# 2_matrix.net
KiCad netlist of a schematic drawn in Altium Designer
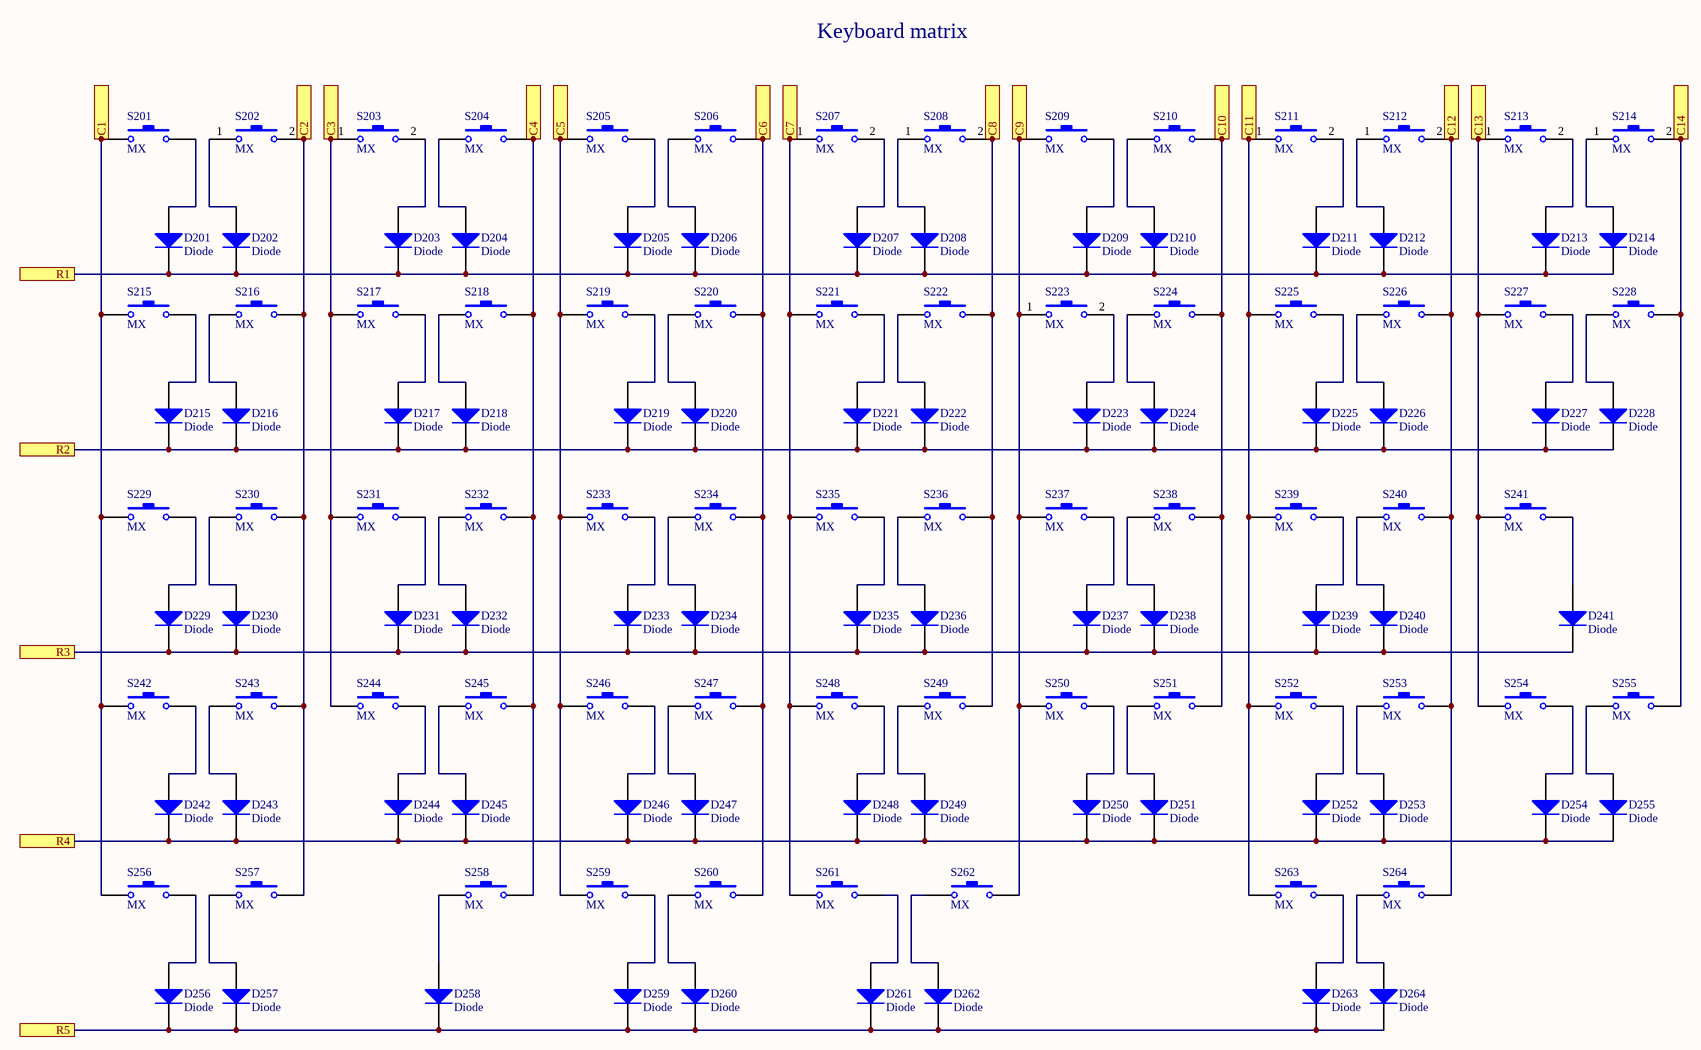
[diagram p0: 2_matrix.SchDoc]

(export (version "E")
  (design (tool "Eeschema 10.0.6"))
  (components
    (comp (ref "D201")
      (value "Diode")
      (footprint "SOD-123")
      (description "Default Diode")
      (fields (field (name "LCSC PART #") "C81598") (field (name "MRF.PART") "1N4148W"))
      (libsource (lib "Miscellaneous Devices") (part "Diode"))
    )
    (comp (ref "D202")
      (value "Diode")
      (footprint "SOD-123")
      (description "Default Diode")
      (fields (field (name "LCSC PART #") "C81598") (field (name "MRF.PART") "1N4148W"))
      (libsource (lib "Miscellaneous Devices") (part "Diode"))
    )
    (comp (ref "D203")
      (value "Diode")
      (footprint "SOD-123")
      (description "Default Diode")
      (fields (field (name "LCSC PART #") "C81598") (field (name "MRF.PART") "1N4148W"))
      (libsource (lib "Miscellaneous Devices") (part "Diode"))
    )
    (comp (ref "D204")
      (value "Diode")
      (footprint "SOD-123")
      (description "Default Diode")
      (fields (field (name "LCSC PART #") "C81598") (field (name "MRF.PART") "1N4148W"))
      (libsource (lib "Miscellaneous Devices") (part "Diode"))
    )
    (comp (ref "D205")
      (value "Diode")
      (footprint "SOD-123")
      (description "Default Diode")
      (fields (field (name "LCSC PART #") "C81598") (field (name "MRF.PART") "1N4148W"))
      (libsource (lib "Miscellaneous Devices") (part "Diode"))
    )
    (comp (ref "D206")
      (value "Diode")
      (footprint "SOD-123")
      (description "Default Diode")
      (fields (field (name "LCSC PART #") "C81598") (field (name "MRF.PART") "1N4148W"))
      (libsource (lib "Miscellaneous Devices") (part "Diode"))
    )
    (comp (ref "D207")
      (value "Diode")
      (footprint "SOD-123")
      (description "Default Diode")
      (fields (field (name "LCSC PART #") "C81598") (field (name "MRF.PART") "1N4148W"))
      (libsource (lib "Miscellaneous Devices") (part "Diode"))
    )
    (comp (ref "D208")
      (value "Diode")
      (footprint "SOD-123")
      (description "Default Diode")
      (fields (field (name "LCSC PART #") "C81598") (field (name "MRF.PART") "1N4148W"))
      (libsource (lib "Miscellaneous Devices") (part "Diode"))
    )
    (comp (ref "D209")
      (value "Diode")
      (footprint "SOD-123")
      (description "Default Diode")
      (fields (field (name "LCSC PART #") "C81598") (field (name "MRF.PART") "1N4148W"))
      (libsource (lib "Miscellaneous Devices") (part "Diode"))
    )
    (comp (ref "D210")
      (value "Diode")
      (footprint "SOD-123")
      (description "Default Diode")
      (fields (field (name "LCSC PART #") "C81598") (field (name "MRF.PART") "1N4148W"))
      (libsource (lib "Miscellaneous Devices") (part "Diode"))
    )
    (comp (ref "D211")
      (value "Diode")
      (footprint "SOD-123")
      (description "Default Diode")
      (fields (field (name "LCSC PART #") "C81598") (field (name "MRF.PART") "1N4148W"))
      (libsource (lib "Miscellaneous Devices") (part "Diode"))
    )
    (comp (ref "D212")
      (value "Diode")
      (footprint "SOD-123")
      (description "Default Diode")
      (fields (field (name "LCSC PART #") "C81598") (field (name "MRF.PART") "1N4148W"))
      (libsource (lib "Miscellaneous Devices") (part "Diode"))
    )
    (comp (ref "D213")
      (value "Diode")
      (footprint "SOD-123")
      (description "Default Diode")
      (fields (field (name "LCSC PART #") "C81598") (field (name "MRF.PART") "1N4148W"))
      (libsource (lib "Miscellaneous Devices") (part "Diode"))
    )
    (comp (ref "D214")
      (value "Diode")
      (footprint "SOD-123")
      (description "Default Diode")
      (fields (field (name "LCSC PART #") "C81598") (field (name "MRF.PART") "1N4148W"))
      (libsource (lib "Miscellaneous Devices") (part "Diode"))
    )
    (comp (ref "D215")
      (value "Diode")
      (footprint "SOD-123")
      (description "Default Diode")
      (fields (field (name "LCSC PART #") "C81598") (field (name "MRF.PART") "1N4148W"))
      (libsource (lib "Miscellaneous Devices") (part "Diode"))
    )
    (comp (ref "D216")
      (value "Diode")
      (footprint "SOD-123")
      (description "Default Diode")
      (fields (field (name "LCSC PART #") "C81598") (field (name "MRF.PART") "1N4148W"))
      (libsource (lib "Miscellaneous Devices") (part "Diode"))
    )
    (comp (ref "D217")
      (value "Diode")
      (footprint "SOD-123")
      (description "Default Diode")
      (fields (field (name "LCSC PART #") "C81598") (field (name "MRF.PART") "1N4148W"))
      (libsource (lib "Miscellaneous Devices") (part "Diode"))
    )
    (comp (ref "D218")
      (value "Diode")
      (footprint "SOD-123")
      (description "Default Diode")
      (fields (field (name "LCSC PART #") "C81598") (field (name "MRF.PART") "1N4148W"))
      (libsource (lib "Miscellaneous Devices") (part "Diode"))
    )
    (comp (ref "D219")
      (value "Diode")
      (footprint "SOD-123")
      (description "Default Diode")
      (fields (field (name "LCSC PART #") "C81598") (field (name "MRF.PART") "1N4148W"))
      (libsource (lib "Miscellaneous Devices") (part "Diode"))
    )
    (comp (ref "D220")
      (value "Diode")
      (footprint "SOD-123")
      (description "Default Diode")
      (fields (field (name "LCSC PART #") "C81598") (field (name "MRF.PART") "1N4148W"))
      (libsource (lib "Miscellaneous Devices") (part "Diode"))
    )
    (comp (ref "D221")
      (value "Diode")
      (footprint "SOD-123")
      (description "Default Diode")
      (fields (field (name "LCSC PART #") "C81598") (field (name "MRF.PART") "1N4148W"))
      (libsource (lib "Miscellaneous Devices") (part "Diode"))
    )
    (comp (ref "D222")
      (value "Diode")
      (footprint "SOD-123")
      (description "Default Diode")
      (fields (field (name "LCSC PART #") "C81598") (field (name "MRF.PART") "1N4148W"))
      (libsource (lib "Miscellaneous Devices") (part "Diode"))
    )
    (comp (ref "D223")
      (value "Diode")
      (footprint "SOD-123")
      (description "Default Diode")
      (fields (field (name "LCSC PART #") "C81598") (field (name "MRF.PART") "1N4148W"))
      (libsource (lib "Miscellaneous Devices") (part "Diode"))
    )
    (comp (ref "D224")
      (value "Diode")
      (footprint "SOD-123")
      (description "Default Diode")
      (fields (field (name "LCSC PART #") "C81598") (field (name "MRF.PART") "1N4148W"))
      (libsource (lib "Miscellaneous Devices") (part "Diode"))
    )
    (comp (ref "D225")
      (value "Diode")
      (footprint "SOD-123")
      (description "Default Diode")
      (fields (field (name "LCSC PART #") "C81598") (field (name "MRF.PART") "1N4148W"))
      (libsource (lib "Miscellaneous Devices") (part "Diode"))
    )
    (comp (ref "D226")
      (value "Diode")
      (footprint "SOD-123")
      (description "Default Diode")
      (fields (field (name "LCSC PART #") "C81598") (field (name "MRF.PART") "1N4148W"))
      (libsource (lib "Miscellaneous Devices") (part "Diode"))
    )
    (comp (ref "D227")
      (value "Diode")
      (footprint "SOD-123")
      (description "Default Diode")
      (fields (field (name "LCSC PART #") "C81598") (field (name "MRF.PART") "1N4148W"))
      (libsource (lib "Miscellaneous Devices") (part "Diode"))
    )
    (comp (ref "D228")
      (value "Diode")
      (footprint "SOD-123")
      (description "Default Diode")
      (fields (field (name "LCSC PART #") "C81598") (field (name "MRF.PART") "1N4148W"))
      (libsource (lib "Miscellaneous Devices") (part "Diode"))
    )
    (comp (ref "D229")
      (value "Diode")
      (footprint "SOD-123")
      (description "Default Diode")
      (fields (field (name "LCSC PART #") "C81598") (field (name "MRF.PART") "1N4148W"))
      (libsource (lib "Miscellaneous Devices") (part "Diode"))
    )
    (comp (ref "D230")
      (value "Diode")
      (footprint "SOD-123")
      (description "Default Diode")
      (fields (field (name "LCSC PART #") "C81598") (field (name "MRF.PART") "1N4148W"))
      (libsource (lib "Miscellaneous Devices") (part "Diode"))
    )
    (comp (ref "D231")
      (value "Diode")
      (footprint "SOD-123")
      (description "Default Diode")
      (fields (field (name "LCSC PART #") "C81598") (field (name "MRF.PART") "1N4148W"))
      (libsource (lib "Miscellaneous Devices") (part "Diode"))
    )
    (comp (ref "D232")
      (value "Diode")
      (footprint "SOD-123")
      (description "Default Diode")
      (fields (field (name "LCSC PART #") "C81598") (field (name "MRF.PART") "1N4148W"))
      (libsource (lib "Miscellaneous Devices") (part "Diode"))
    )
    (comp (ref "D233")
      (value "Diode")
      (footprint "SOD-123")
      (description "Default Diode")
      (fields (field (name "LCSC PART #") "C81598") (field (name "MRF.PART") "1N4148W"))
      (libsource (lib "Miscellaneous Devices") (part "Diode"))
    )
    (comp (ref "D234")
      (value "Diode")
      (footprint "SOD-123")
      (description "Default Diode")
      (fields (field (name "LCSC PART #") "C81598") (field (name "MRF.PART") "1N4148W"))
      (libsource (lib "Miscellaneous Devices") (part "Diode"))
    )
    (comp (ref "D235")
      (value "Diode")
      (footprint "SOD-123")
      (description "Default Diode")
      (fields (field (name "LCSC PART #") "C81598") (field (name "MRF.PART") "1N4148W"))
      (libsource (lib "Miscellaneous Devices") (part "Diode"))
    )
    (comp (ref "D236")
      (value "Diode")
      (footprint "SOD-123")
      (description "Default Diode")
      (fields (field (name "LCSC PART #") "C81598") (field (name "MRF.PART") "1N4148W"))
      (libsource (lib "Miscellaneous Devices") (part "Diode"))
    )
    (comp (ref "D237")
      (value "Diode")
      (footprint "SOD-123")
      (description "Default Diode")
      (fields (field (name "LCSC PART #") "C81598") (field (name "MRF.PART") "1N4148W"))
      (libsource (lib "Miscellaneous Devices") (part "Diode"))
    )
    (comp (ref "D238")
      (value "Diode")
      (footprint "SOD-123")
      (description "Default Diode")
      (fields (field (name "LCSC PART #") "C81598") (field (name "MRF.PART") "1N4148W"))
      (libsource (lib "Miscellaneous Devices") (part "Diode"))
    )
    (comp (ref "D239")
      (value "Diode")
      (footprint "SOD-123")
      (description "Default Diode")
      (fields (field (name "LCSC PART #") "C81598") (field (name "MRF.PART") "1N4148W"))
      (libsource (lib "Miscellaneous Devices") (part "Diode"))
    )
    (comp (ref "D240")
      (value "Diode")
      (footprint "SOD-123")
      (description "Default Diode")
      (fields (field (name "LCSC PART #") "C81598") (field (name "MRF.PART") "1N4148W"))
      (libsource (lib "Miscellaneous Devices") (part "Diode"))
    )
    (comp (ref "D241")
      (value "Diode")
      (footprint "SOD-123")
      (description "Default Diode")
      (fields (field (name "LCSC PART #") "C81598") (field (name "MRF.PART") "1N4148W"))
      (libsource (lib "Miscellaneous Devices") (part "Diode"))
    )
    (comp (ref "D242")
      (value "Diode")
      (footprint "SOD-123")
      (description "Default Diode")
      (fields (field (name "LCSC PART #") "C81598") (field (name "MRF.PART") "1N4148W"))
      (libsource (lib "Miscellaneous Devices") (part "Diode"))
    )
    (comp (ref "D243")
      (value "Diode")
      (footprint "SOD-123")
      (description "Default Diode")
      (fields (field (name "LCSC PART #") "C81598") (field (name "MRF.PART") "1N4148W"))
      (libsource (lib "Miscellaneous Devices") (part "Diode"))
    )
    (comp (ref "D244")
      (value "Diode")
      (footprint "SOD-123")
      (description "Default Diode")
      (fields (field (name "LCSC PART #") "C81598") (field (name "MRF.PART") "1N4148W"))
      (libsource (lib "Miscellaneous Devices") (part "Diode"))
    )
    (comp (ref "D245")
      (value "Diode")
      (footprint "SOD-123")
      (description "Default Diode")
      (fields (field (name "LCSC PART #") "C81598") (field (name "MRF.PART") "1N4148W"))
      (libsource (lib "Miscellaneous Devices") (part "Diode"))
    )
    (comp (ref "D246")
      (value "Diode")
      (footprint "SOD-123")
      (description "Default Diode")
      (fields (field (name "LCSC PART #") "C81598") (field (name "MRF.PART") "1N4148W"))
      (libsource (lib "Miscellaneous Devices") (part "Diode"))
    )
    (comp (ref "D247")
      (value "Diode")
      (footprint "SOD-123")
      (description "Default Diode")
      (fields (field (name "LCSC PART #") "C81598") (field (name "MRF.PART") "1N4148W"))
      (libsource (lib "Miscellaneous Devices") (part "Diode"))
    )
    (comp (ref "D248")
      (value "Diode")
      (footprint "SOD-123")
      (description "Default Diode")
      (fields (field (name "LCSC PART #") "C81598") (field (name "MRF.PART") "1N4148W"))
      (libsource (lib "Miscellaneous Devices") (part "Diode"))
    )
    (comp (ref "D249")
      (value "Diode")
      (footprint "SOD-123")
      (description "Default Diode")
      (fields (field (name "LCSC PART #") "C81598") (field (name "MRF.PART") "1N4148W"))
      (libsource (lib "Miscellaneous Devices") (part "Diode"))
    )
    (comp (ref "D250")
      (value "Diode")
      (footprint "SOD-123")
      (description "Default Diode")
      (fields (field (name "LCSC PART #") "C81598") (field (name "MRF.PART") "1N4148W"))
      (libsource (lib "Miscellaneous Devices") (part "Diode"))
    )
    (comp (ref "D251")
      (value "Diode")
      (footprint "SOD-123")
      (description "Default Diode")
      (fields (field (name "LCSC PART #") "C81598") (field (name "MRF.PART") "1N4148W"))
      (libsource (lib "Miscellaneous Devices") (part "Diode"))
    )
    (comp (ref "D252")
      (value "Diode")
      (footprint "SOD-123")
      (description "Default Diode")
      (fields (field (name "LCSC PART #") "C81598") (field (name "MRF.PART") "1N4148W"))
      (libsource (lib "Miscellaneous Devices") (part "Diode"))
    )
    (comp (ref "D253")
      (value "Diode")
      (footprint "SOD-123")
      (description "Default Diode")
      (fields (field (name "LCSC PART #") "C81598") (field (name "MRF.PART") "1N4148W"))
      (libsource (lib "Miscellaneous Devices") (part "Diode"))
    )
    (comp (ref "D254")
      (value "Diode")
      (footprint "SOD-123")
      (description "Default Diode")
      (fields (field (name "LCSC PART #") "C81598") (field (name "MRF.PART") "1N4148W"))
      (libsource (lib "Miscellaneous Devices") (part "Diode"))
    )
    (comp (ref "D255")
      (value "Diode")
      (footprint "SOD-123")
      (description "Default Diode")
      (fields (field (name "LCSC PART #") "C81598") (field (name "MRF.PART") "1N4148W"))
      (libsource (lib "Miscellaneous Devices") (part "Diode"))
    )
    (comp (ref "D256")
      (value "Diode")
      (footprint "SOD-123")
      (description "Default Diode")
      (fields (field (name "LCSC PART #") "C81598") (field (name "MRF.PART") "1N4148W"))
      (libsource (lib "Miscellaneous Devices") (part "Diode"))
    )
    (comp (ref "D257")
      (value "Diode")
      (footprint "SOD-123")
      (description "Default Diode")
      (fields (field (name "LCSC PART #") "C81598") (field (name "MRF.PART") "1N4148W"))
      (libsource (lib "Miscellaneous Devices") (part "Diode"))
    )
    (comp (ref "D258")
      (value "Diode")
      (footprint "SOD-123")
      (description "Default Diode")
      (fields (field (name "LCSC PART #") "C81598") (field (name "MRF.PART") "1N4148W"))
      (libsource (lib "Miscellaneous Devices") (part "Diode"))
    )
    (comp (ref "D259")
      (value "Diode")
      (footprint "SOD-123")
      (description "Default Diode")
      (fields (field (name "LCSC PART #") "C81598") (field (name "MRF.PART") "1N4148W"))
      (libsource (lib "Miscellaneous Devices") (part "Diode"))
    )
    (comp (ref "D260")
      (value "Diode")
      (footprint "SOD-123")
      (description "Default Diode")
      (fields (field (name "LCSC PART #") "C81598") (field (name "MRF.PART") "1N4148W"))
      (libsource (lib "Miscellaneous Devices") (part "Diode"))
    )
    (comp (ref "D261")
      (value "Diode")
      (footprint "SOD-123")
      (description "Default Diode")
      (fields (field (name "LCSC PART #") "C81598") (field (name "MRF.PART") "1N4148W"))
      (libsource (lib "Miscellaneous Devices") (part "Diode"))
    )
    (comp (ref "D262")
      (value "Diode")
      (footprint "SOD-123")
      (description "Default Diode")
      (fields (field (name "LCSC PART #") "C81598") (field (name "MRF.PART") "1N4148W"))
      (libsource (lib "Miscellaneous Devices") (part "Diode"))
    )
    (comp (ref "D263")
      (value "Diode")
      (footprint "SOD-123")
      (description "Default Diode")
      (fields (field (name "LCSC PART #") "C81598") (field (name "MRF.PART") "1N4148W"))
      (libsource (lib "Miscellaneous Devices") (part "Diode"))
    )
    (comp (ref "D264")
      (value "Diode")
      (footprint "SOD-123")
      (description "Default Diode")
      (fields (field (name "LCSC PART #") "C81598") (field (name "MRF.PART") "1N4148W"))
      (libsource (lib "Miscellaneous Devices") (part "Diode"))
    )
    (comp (ref "S201")
      (value "MX")
      (footprint "ALPS-switch - 1.25U - switched pol")
      (description "Switch")
      (libsource (lib "Miscellaneous Devices") (part "SW-PB"))
    )
    (comp (ref "S202")
      (value "MX")
      (footprint "Alps-switch - switched pol")
      (description "Switch")
      (libsource (lib "") (part "SW-PB_2"))
    )
    (comp (ref "S203")
      (value "MX")
      (footprint "Alps-switch")
      (description "Switch")
      (libsource (lib "") (part "SW-PB_2"))
    )
    (comp (ref "S204")
      (value "MX")
      (footprint "Alps-switch")
      (description "Switch")
      (libsource (lib "Miscellaneous Devices") (part "SW-PB"))
    )
    (comp (ref "S205")
      (value "MX")
      (footprint "Alps-switch")
      (description "Switch")
      (libsource (lib "Miscellaneous Devices") (part "SW-PB"))
    )
    (comp (ref "S206")
      (value "MX")
      (footprint "Alps-switch - switched pol")
      (description "Switch")
      (libsource (lib "Miscellaneous Devices") (part "SW-PB"))
    )
    (comp (ref "S207")
      (value "MX")
      (footprint "Alps-switch")
      (description "Switch")
      (libsource (lib "") (part "SW-PB_2"))
    )
    (comp (ref "S208")
      (value "MX")
      (footprint "Alps-switch - switched pol")
      (description "Switch")
      (libsource (lib "") (part "SW-PB_2"))
    )
    (comp (ref "S209")
      (value "MX")
      (footprint "Alps-switch")
      (description "Switch")
      (libsource (lib "Miscellaneous Devices") (part "SW-PB"))
    )
    (comp (ref "S210")
      (value "MX")
      (footprint "Alps-switch - switched pol")
      (description "Switch")
      (libsource (lib "Miscellaneous Devices") (part "SW-PB"))
    )
    (comp (ref "S211")
      (value "MX")
      (footprint "Alps-switch")
      (description "Switch")
      (libsource (lib "") (part "SW-PB_2"))
    )
    (comp (ref "S212")
      (value "MX")
      (footprint "Alps-switch - switched pol")
      (description "Switch")
      (libsource (lib "") (part "SW-PB_2"))
    )
    (comp (ref "S213")
      (value "MX")
      (footprint "Alps-switch")
      (description "Switch")
      (libsource (lib "") (part "SW-PB_2"))
    )
    (comp (ref "S214")
      (value "MX")
      (footprint "ALPS-switch - 1.25U - switched pol")
      (description "Switch")
      (libsource (lib "") (part "SW-PB_2"))
    )
    (comp (ref "S215")
      (value "MX")
      (footprint "ALPS-switch - 1.25U")
      (description "TAB")
      (libsource (lib "Miscellaneous Devices") (part "SW-PB"))
    )
    (comp (ref "S216")
      (value "MX")
      (footprint "Alps-switch")
      (description "Switch")
      (libsource (lib "Miscellaneous Devices") (part "SW-PB"))
    )
    (comp (ref "S217")
      (value "MX")
      (footprint "Alps-switch")
      (description "Switch")
      (libsource (lib "Miscellaneous Devices") (part "SW-PB"))
    )
    (comp (ref "S218")
      (value "MX")
      (footprint "Alps-switch - switched pol")
      (description "Switch")
      (libsource (lib "Miscellaneous Devices") (part "SW-PB"))
    )
    (comp (ref "S219")
      (value "MX")
      (footprint "Alps-switch")
      (description "Switch")
      (libsource (lib "Miscellaneous Devices") (part "SW-PB"))
    )
    (comp (ref "S220")
      (value "MX")
      (footprint "Alps-switch")
      (description "Switch")
      (libsource (lib "Miscellaneous Devices") (part "SW-PB"))
    )
    (comp (ref "S221")
      (value "MX")
      (footprint "Alps-switch")
      (description "Switch")
      (libsource (lib "Miscellaneous Devices") (part "SW-PB"))
    )
    (comp (ref "S222")
      (value "MX")
      (footprint "Alps-switch")
      (description "Switch")
      (libsource (lib "Miscellaneous Devices") (part "SW-PB"))
    )
    (comp (ref "S223")
      (value "MX")
      (footprint "Alps-switch")
      (description "Switch")
      (libsource (lib "") (part "SW-PB_2"))
    )
    (comp (ref "S224")
      (value "MX")
      (footprint "Alps-switch - switched pol")
      (description "Switch")
      (libsource (lib "Miscellaneous Devices") (part "SW-PB"))
    )
    (comp (ref "S225")
      (value "MX")
      (footprint "Alps-switch")
      (description "Switch")
      (libsource (lib "Miscellaneous Devices") (part "SW-PB"))
    )
    (comp (ref "S226")
      (value "MX")
      (footprint "Alps-switch - switched pol")
      (description "Switch")
      (libsource (lib "Miscellaneous Devices") (part "SW-PB"))
    )
    (comp (ref "S227")
      (value "MX")
      (footprint "Alps-switch")
      (description "Switch")
      (libsource (lib "") (part "SW-PB_1"))
    )
    (comp (ref "S228")
      (value "MX")
      (footprint "ALPS-SWITCH - ENTER - AEKISO")
      (description "Switch")
      (libsource (lib "Miscellaneous Devices") (part "SW-PB"))
    )
    (comp (ref "S229")
      (value "MX")
      (footprint "ALPS-switch - 2U - no stab")
      (description "Switch")
      (libsource (lib "Miscellaneous Devices") (part "SW-PB"))
    )
    (comp (ref "S230")
      (value "MX")
      (footprint "Alps-switch")
      (description "Switch")
      (libsource (lib "Miscellaneous Devices") (part "SW-PB"))
    )
    (comp (ref "S231")
      (value "MX")
      (footprint "Alps-switch")
      (description "Switch")
      (libsource (lib "Miscellaneous Devices") (part "SW-PB"))
    )
    (comp (ref "S232")
      (value "MX")
      (footprint "Alps-switch - switched pol")
      (description "Switch")
      (libsource (lib "Miscellaneous Devices") (part "SW-PB"))
    )
    (comp (ref "S233")
      (value "MX")
      (footprint "Alps-switch")
      (description "Switch")
      (libsource (lib "Miscellaneous Devices") (part "SW-PB"))
    )
    (comp (ref "S234")
      (value "MX")
      (footprint "Alps-switch - switched pol")
      (description "Switch")
      (libsource (lib "") (part "SW-PB_1"))
    )
    (comp (ref "S235")
      (value "MX")
      (footprint "Alps-switch - switched pol")
      (description "Switch")
      (libsource (lib "") (part "SW-PB_1"))
    )
    (comp (ref "S236")
      (value "MX")
      (footprint "Alps-switch")
      (description "Switch")
      (libsource (lib "") (part "SW-PB_1"))
    )
    (comp (ref "S237")
      (value "MX")
      (footprint "Alps-switch - switched pol")
      (description "Switch")
      (libsource (lib "") (part "SW-PB_1"))
    )
    (comp (ref "S238")
      (value "MX")
      (footprint "Alps-switch - switched pol")
      (description "Switch")
      (libsource (lib "Miscellaneous Devices") (part "SW-PB"))
    )
    (comp (ref "S239")
      (value "MX")
      (footprint "Alps-switch")
      (description "Switch")
      (libsource (lib "Miscellaneous Devices") (part "SW-PB"))
    )
    (comp (ref "S240")
      (value "MX")
      (footprint "Alps-switch - switched pol")
      (description "Switch")
      (libsource (lib "Miscellaneous Devices") (part "SW-PB"))
    )
    (comp (ref "S241")
      (value "MX")
      (footprint "Alps-switch")
      (description "Switch")
      (libsource (lib "Miscellaneous Devices") (part "SW-PB"))
    )
    (comp (ref "S242")
      (value "MX")
      (footprint "ALPS-switch - 1.5U")
      (description "Switch")
      (libsource (lib "Miscellaneous Devices") (part "SW-PB"))
    )
    (comp (ref "S243")
      (value "MX")
      (footprint "Alps-switch - switched pol")
      (description "Switch")
      (libsource (lib "Miscellaneous Devices") (part "SW-PB"))
    )
    (comp (ref "S244")
      (value "MX")
      (footprint "Alps-switch - switched pol")
      (description "Switch")
      (libsource (lib "") (part "SW-PB_1"))
    )
    (comp (ref "S245")
      (value "MX")
      (footprint "Alps-switch")
      (description "Switch")
      (libsource (lib "") (part "SW-PB_1"))
    )
    (comp (ref "S246")
      (value "MX")
      (footprint "Alps-switch - switched pol")
      (description "Switch")
      (libsource (lib "") (part "SW-PB_1"))
    )
    (comp (ref "S247")
      (value "MX")
      (footprint "Alps-switch")
      (description "Switch")
      (libsource (lib "") (part "SW-PB_1"))
    )
    (comp (ref "S248")
      (value "MX")
      (footprint "Alps-switch - switched pol")
      (description "Switch")
      (libsource (lib "") (part "SW-PB_1"))
    )
    (comp (ref "S249")
      (value "MX")
      (footprint "Alps-switch - switched pol")
      (description "Switch")
      (libsource (lib "Miscellaneous Devices") (part "SW-PB"))
    )
    (comp (ref "S250")
      (value "MX")
      (footprint "Alps-switch - switched pol")
      (description "Switch")
      (libsource (lib "") (part "SW-PB_1"))
    )
    (comp (ref "S251")
      (value "MX")
      (footprint "Alps-switch - switched pol")
      (description "Switch")
      (libsource (lib "Miscellaneous Devices") (part "SW-PB"))
    )
    (comp (ref "S252")
      (value "MX")
      (footprint "Alps-switch - switched pol")
      (description "Switch")
      (libsource (lib "") (part "SW-PB_1"))
    )
    (comp (ref "S253")
      (value "MX")
      (footprint "Alps-switch")
      (description "Switch")
      (libsource (lib "") (part "SW-PB_1"))
    )
    (comp (ref "S254")
      (value "MX")
      (footprint "ALPS-switch - AEKISO r_shift")
      (description "Switch")
      (libsource (lib "Miscellaneous Devices") (part "SW-PB"))
    )
    (comp (ref "S255")
      (value "MX")
      (footprint "Alps-switch")
      (description "Switch")
      (libsource (lib "Miscellaneous Devices") (part "SW-PB"))
    )
    (comp (ref "S256")
      (value "MX")
      (footprint "Alps-switch - switched pol")
      (description "Switch")
      (libsource (lib "Miscellaneous Devices") (part "SW-PB"))
    )
    (comp (ref "S257")
      (value "MX")
      (footprint "ALPS-switch - L_WIN - AEKISO60")
      (description "Switch")
      (libsource (lib "Miscellaneous Devices") (part "SW-PB"))
    )
    (comp (ref "S258")
      (value "MX")
      (footprint "ALPS-switch - L_alt - AEKISO60")
      (description "Switch")
      (libsource (lib "Miscellaneous Devices") (part "SW-PB"))
    )
    (comp (ref "S259")
      (value "MX")
      (footprint "ALPS-SWITCH - L SPLIT SPACE - AEKISO60")
      (description "Switch")
      (libsource (lib "Miscellaneous Devices") (part "SW-PB"))
    )
    (comp (ref "S260")
      (value "MX")
      (footprint "ALPS-SWITCH - SPACE - AEKISO60")
      (description "Switch")
      (libsource (lib "Miscellaneous Devices") (part "SW-PB"))
    )
    (comp (ref "S261")
      (value "MX")
      (footprint "ALPS-switch - R split space - AEKISO60")
      (description "Switch")
      (libsource (lib "Miscellaneous Devices") (part "SW-PB"))
    )
    (comp (ref "S262")
      (value "MX")
      (footprint "ALPS-switch - R_alt - AEKISO60")
      (description "Switch")
      (libsource (lib "Miscellaneous Devices") (part "SW-PB"))
    )
    (comp (ref "S263")
      (value "MX")
      (footprint "ALPS-SWITCH - R_WIN - AEKISO60")
      (description "Switch")
      (libsource (lib "Miscellaneous Devices") (part "SW-PB"))
    )
    (comp (ref "S264")
      (value "MX")
      (footprint "ALPS-switch - 1.25U - switched pol")
      (description "Switch")
      (libsource (lib "Miscellaneous Devices") (part "SW-PB"))
    )
  )
  (nets
    (net (code "1") (name "/C1") (class "Default")
      (node (ref "S201") (pin "2") (pinfunction "2_2") (pintype "passive"))
      (node (ref "S215") (pin "1") (pinfunction "1_1") (pintype "passive"))
      (node (ref "S229") (pin "1") (pinfunction "1_1") (pintype "passive"))
      (node (ref "S242") (pin "1") (pinfunction "1_1") (pintype "passive"))
      (node (ref "S256") (pin "1") (pinfunction "1_1") (pintype "passive"))
    )
    (net (code "2") (name "/C2") (class "Default")
      (node (ref "S202") (pin "2") (pinfunction "2_2") (pintype "passive"))
      (node (ref "S216") (pin "2") (pinfunction "2_2") (pintype "passive"))
      (node (ref "S230") (pin "2") (pinfunction "2_2") (pintype "passive"))
      (node (ref "S243") (pin "2") (pinfunction "2_2") (pintype "passive"))
      (node (ref "S257") (pin "1") (pinfunction "1_1") (pintype "passive"))
    )
    (net (code "3") (name "/C3") (class "Default")
      (node (ref "S203") (pin "1") (pinfunction "1_1") (pintype "passive"))
      (node (ref "S217") (pin "1") (pinfunction "1_1") (pintype "passive"))
      (node (ref "S231") (pin "1") (pinfunction "1_1") (pintype "passive"))
      (node (ref "S244") (pin "2") (pinfunction "2_2") (pintype "passive"))
    )
    (net (code "4") (name "/C4") (class "Default")
      (node (ref "S204") (pin "2") (pinfunction "2_2") (pintype "passive"))
      (node (ref "S218") (pin "2") (pinfunction "2_2") (pintype "passive"))
      (node (ref "S232") (pin "2") (pinfunction "2_2") (pintype "passive"))
      (node (ref "S245") (pin "1") (pinfunction "1_1") (pintype "passive"))
      (node (ref "S258") (pin "2") (pinfunction "2_2") (pintype "passive"))
    )
    (net (code "5") (name "/C5") (class "Default")
      (node (ref "S205") (pin "1") (pinfunction "1_1") (pintype "passive"))
      (node (ref "S219") (pin "1") (pinfunction "1_1") (pintype "passive"))
      (node (ref "S233") (pin "1") (pinfunction "1_1") (pintype "passive"))
      (node (ref "S246") (pin "2") (pinfunction "2_2") (pintype "passive"))
      (node (ref "S259") (pin "1") (pinfunction "1_1") (pintype "passive"))
    )
    (net (code "6") (name "/C6") (class "Default")
      (node (ref "S206") (pin "2") (pinfunction "2_2") (pintype "passive"))
      (node (ref "S220") (pin "2") (pinfunction "2_2") (pintype "passive"))
      (node (ref "S234") (pin "1") (pinfunction "1_1") (pintype "passive"))
      (node (ref "S247") (pin "1") (pinfunction "1_1") (pintype "passive"))
      (node (ref "S260") (pin "1") (pinfunction "1_1") (pintype "passive"))
    )
    (net (code "7") (name "/C7") (class "Default")
      (node (ref "S207") (pin "1") (pinfunction "1_1") (pintype "passive"))
      (node (ref "S221") (pin "1") (pinfunction "1_1") (pintype "passive"))
      (node (ref "S235") (pin "2") (pinfunction "2_2") (pintype "passive"))
      (node (ref "S248") (pin "2") (pinfunction "2_2") (pintype "passive"))
      (node (ref "S261") (pin "2") (pinfunction "2_2") (pintype "passive"))
    )
    (net (code "8") (name "/C8") (class "Default")
      (node (ref "S208") (pin "2") (pinfunction "2_2") (pintype "passive"))
      (node (ref "S222") (pin "2") (pinfunction "2_2") (pintype "passive"))
      (node (ref "S236") (pin "1") (pinfunction "1_1") (pintype "passive"))
      (node (ref "S249") (pin "2") (pinfunction "2_2") (pintype "passive"))
    )
    (net (code "9") (name "/C9") (class "Default")
      (node (ref "S209") (pin "1") (pinfunction "1_1") (pintype "passive"))
      (node (ref "S223") (pin "1") (pinfunction "1_1") (pintype "passive"))
      (node (ref "S237") (pin "2") (pinfunction "2_2") (pintype "passive"))
      (node (ref "S250") (pin "2") (pinfunction "2_2") (pintype "passive"))
      (node (ref "S262") (pin "2") (pinfunction "2_2") (pintype "passive"))
    )
    (net (code "10") (name "/C10") (class "Default")
      (node (ref "S210") (pin "2") (pinfunction "2_2") (pintype "passive"))
      (node (ref "S224") (pin "2") (pinfunction "2_2") (pintype "passive"))
      (node (ref "S238") (pin "2") (pinfunction "2_2") (pintype "passive"))
      (node (ref "S251") (pin "2") (pinfunction "2_2") (pintype "passive"))
    )
    (net (code "11") (name "/C11") (class "Default")
      (node (ref "S211") (pin "1") (pinfunction "1_1") (pintype "passive"))
      (node (ref "S225") (pin "1") (pinfunction "1_1") (pintype "passive"))
      (node (ref "S239") (pin "1") (pinfunction "1_1") (pintype "passive"))
      (node (ref "S252") (pin "2") (pinfunction "2_2") (pintype "passive"))
      (node (ref "S263") (pin "2") (pinfunction "2_2") (pintype "passive"))
    )
    (net (code "12") (name "/C12") (class "Default")
      (node (ref "S212") (pin "2") (pinfunction "2_2") (pintype "passive"))
      (node (ref "S226") (pin "2") (pinfunction "2_2") (pintype "passive"))
      (node (ref "S240") (pin "2") (pinfunction "2_2") (pintype "passive"))
      (node (ref "S253") (pin "1") (pinfunction "1_1") (pintype "passive"))
      (node (ref "S264") (pin "2") (pinfunction "2_2") (pintype "passive"))
    )
    (net (code "13") (name "/C13") (class "Default")
      (node (ref "S213") (pin "1") (pinfunction "1_1") (pintype "passive"))
      (node (ref "S227") (pin "2") (pinfunction "2_2") (pintype "passive"))
      (node (ref "S241") (pin "1") (pinfunction "1_1") (pintype "passive"))
      (node (ref "S254") (pin "2") (pinfunction "2_2") (pintype "passive"))
    )
    (net (code "14") (name "/C14") (class "Default")
      (node (ref "S214") (pin "2") (pinfunction "2_2") (pintype "passive"))
      (node (ref "S228") (pin "2") (pinfunction "2_2") (pintype "passive"))
      (node (ref "S255") (pin "2") (pinfunction "2_2") (pintype "passive"))
    )
    (net (code "15") (name "/R1") (class "Default")
      (node (ref "D201") (pin "2") (pinfunction "K_2") (pintype "passive"))
      (node (ref "D202") (pin "2") (pinfunction "K_2") (pintype "passive"))
      (node (ref "D203") (pin "2") (pinfunction "K_2") (pintype "passive"))
      (node (ref "D204") (pin "2") (pinfunction "K_2") (pintype "passive"))
      (node (ref "D205") (pin "2") (pinfunction "K_2") (pintype "passive"))
      (node (ref "D206") (pin "2") (pinfunction "K_2") (pintype "passive"))
      (node (ref "D207") (pin "2") (pinfunction "K_2") (pintype "passive"))
      (node (ref "D208") (pin "2") (pinfunction "K_2") (pintype "passive"))
      (node (ref "D209") (pin "2") (pinfunction "K_2") (pintype "passive"))
      (node (ref "D210") (pin "2") (pinfunction "K_2") (pintype "passive"))
      (node (ref "D211") (pin "2") (pinfunction "K_2") (pintype "passive"))
      (node (ref "D212") (pin "2") (pinfunction "K_2") (pintype "passive"))
      (node (ref "D213") (pin "2") (pinfunction "K_2") (pintype "passive"))
      (node (ref "D214") (pin "2") (pinfunction "K_2") (pintype "passive"))
    )
    (net (code "16") (name "/R2") (class "Default")
      (node (ref "D215") (pin "2") (pinfunction "K_2") (pintype "passive"))
      (node (ref "D216") (pin "2") (pinfunction "K_2") (pintype "passive"))
      (node (ref "D217") (pin "2") (pinfunction "K_2") (pintype "passive"))
      (node (ref "D218") (pin "2") (pinfunction "K_2") (pintype "passive"))
      (node (ref "D219") (pin "2") (pinfunction "K_2") (pintype "passive"))
      (node (ref "D220") (pin "2") (pinfunction "K_2") (pintype "passive"))
      (node (ref "D221") (pin "2") (pinfunction "K_2") (pintype "passive"))
      (node (ref "D222") (pin "2") (pinfunction "K_2") (pintype "passive"))
      (node (ref "D223") (pin "2") (pinfunction "K_2") (pintype "passive"))
      (node (ref "D224") (pin "2") (pinfunction "K_2") (pintype "passive"))
      (node (ref "D225") (pin "2") (pinfunction "K_2") (pintype "passive"))
      (node (ref "D226") (pin "2") (pinfunction "K_2") (pintype "passive"))
      (node (ref "D227") (pin "2") (pinfunction "K_2") (pintype "passive"))
      (node (ref "D228") (pin "2") (pinfunction "K_2") (pintype "passive"))
    )
    (net (code "17") (name "/R3") (class "Default")
      (node (ref "D229") (pin "2") (pinfunction "K_2") (pintype "passive"))
      (node (ref "D230") (pin "2") (pinfunction "K_2") (pintype "passive"))
      (node (ref "D231") (pin "2") (pinfunction "K_2") (pintype "passive"))
      (node (ref "D232") (pin "2") (pinfunction "K_2") (pintype "passive"))
      (node (ref "D233") (pin "2") (pinfunction "K_2") (pintype "passive"))
      (node (ref "D234") (pin "2") (pinfunction "K_2") (pintype "passive"))
      (node (ref "D235") (pin "2") (pinfunction "K_2") (pintype "passive"))
      (node (ref "D236") (pin "2") (pinfunction "K_2") (pintype "passive"))
      (node (ref "D237") (pin "2") (pinfunction "K_2") (pintype "passive"))
      (node (ref "D238") (pin "2") (pinfunction "K_2") (pintype "passive"))
      (node (ref "D239") (pin "2") (pinfunction "K_2") (pintype "passive"))
      (node (ref "D240") (pin "2") (pinfunction "K_2") (pintype "passive"))
      (node (ref "D241") (pin "2") (pinfunction "K_2") (pintype "passive"))
    )
    (net (code "18") (name "/R4") (class "Default")
      (node (ref "D242") (pin "2") (pinfunction "K_2") (pintype "passive"))
      (node (ref "D243") (pin "2") (pinfunction "K_2") (pintype "passive"))
      (node (ref "D244") (pin "2") (pinfunction "K_2") (pintype "passive"))
      (node (ref "D245") (pin "2") (pinfunction "K_2") (pintype "passive"))
      (node (ref "D246") (pin "2") (pinfunction "K_2") (pintype "passive"))
      (node (ref "D247") (pin "2") (pinfunction "K_2") (pintype "passive"))
      (node (ref "D248") (pin "2") (pinfunction "K_2") (pintype "passive"))
      (node (ref "D249") (pin "2") (pinfunction "K_2") (pintype "passive"))
      (node (ref "D250") (pin "2") (pinfunction "K_2") (pintype "passive"))
      (node (ref "D251") (pin "2") (pinfunction "K_2") (pintype "passive"))
      (node (ref "D252") (pin "2") (pinfunction "K_2") (pintype "passive"))
      (node (ref "D253") (pin "2") (pinfunction "K_2") (pintype "passive"))
      (node (ref "D254") (pin "2") (pinfunction "K_2") (pintype "passive"))
      (node (ref "D255") (pin "2") (pinfunction "K_2") (pintype "passive"))
    )
    (net (code "19") (name "/R5") (class "Default")
      (node (ref "D256") (pin "2") (pinfunction "K_2") (pintype "passive"))
      (node (ref "D257") (pin "2") (pinfunction "K_2") (pintype "passive"))
      (node (ref "D258") (pin "2") (pinfunction "K_2") (pintype "passive"))
      (node (ref "D259") (pin "2") (pinfunction "K_2") (pintype "passive"))
      (node (ref "D260") (pin "2") (pinfunction "K_2") (pintype "passive"))
      (node (ref "D261") (pin "2") (pinfunction "K_2") (pintype "passive"))
      (node (ref "D262") (pin "2") (pinfunction "K_2") (pintype "passive"))
      (node (ref "D263") (pin "2") (pinfunction "K_2") (pintype "passive"))
      (node (ref "D264") (pin "2") (pinfunction "K_2") (pintype "passive"))
    )
    (net (code "20") (name "Net-(D201-A)") (class "Default")
      (node (ref "D201") (pin "1") (pinfunction "A_1") (pintype "passive"))
      (node (ref "S201") (pin "1") (pinfunction "1_1") (pintype "passive"))
    )
    (net (code "21") (name "Net-(D202-A)") (class "Default")
      (node (ref "D202") (pin "1") (pinfunction "A_1") (pintype "passive"))
      (node (ref "S202") (pin "1") (pinfunction "1_1") (pintype "passive"))
    )
    (net (code "22") (name "Net-(D203-A)") (class "Default")
      (node (ref "D203") (pin "1") (pinfunction "A_1") (pintype "passive"))
      (node (ref "S203") (pin "2") (pinfunction "2_2") (pintype "passive"))
    )
    (net (code "23") (name "Net-(D204-A)") (class "Default")
      (node (ref "D204") (pin "1") (pinfunction "A_1") (pintype "passive"))
      (node (ref "S204") (pin "1") (pinfunction "1_1") (pintype "passive"))
    )
    (net (code "24") (name "Net-(D205-A)") (class "Default")
      (node (ref "D205") (pin "1") (pinfunction "A_1") (pintype "passive"))
      (node (ref "S205") (pin "2") (pinfunction "2_2") (pintype "passive"))
    )
    (net (code "25") (name "Net-(D206-A)") (class "Default")
      (node (ref "D206") (pin "1") (pinfunction "A_1") (pintype "passive"))
      (node (ref "S206") (pin "1") (pinfunction "1_1") (pintype "passive"))
    )
    (net (code "26") (name "Net-(D207-A)") (class "Default")
      (node (ref "D207") (pin "1") (pinfunction "A_1") (pintype "passive"))
      (node (ref "S207") (pin "2") (pinfunction "2_2") (pintype "passive"))
    )
    (net (code "27") (name "Net-(D208-A)") (class "Default")
      (node (ref "D208") (pin "1") (pinfunction "A_1") (pintype "passive"))
      (node (ref "S208") (pin "1") (pinfunction "1_1") (pintype "passive"))
    )
    (net (code "28") (name "Net-(D209-A)") (class "Default")
      (node (ref "D209") (pin "1") (pinfunction "A_1") (pintype "passive"))
      (node (ref "S209") (pin "2") (pinfunction "2_2") (pintype "passive"))
    )
    (net (code "29") (name "Net-(D210-A)") (class "Default")
      (node (ref "D210") (pin "1") (pinfunction "A_1") (pintype "passive"))
      (node (ref "S210") (pin "1") (pinfunction "1_1") (pintype "passive"))
    )
    (net (code "30") (name "Net-(D211-A)") (class "Default")
      (node (ref "D211") (pin "1") (pinfunction "A_1") (pintype "passive"))
      (node (ref "S211") (pin "2") (pinfunction "2_2") (pintype "passive"))
    )
    (net (code "31") (name "Net-(D212-A)") (class "Default")
      (node (ref "D212") (pin "1") (pinfunction "A_1") (pintype "passive"))
      (node (ref "S212") (pin "1") (pinfunction "1_1") (pintype "passive"))
    )
    (net (code "32") (name "Net-(D213-A)") (class "Default")
      (node (ref "D213") (pin "1") (pinfunction "A_1") (pintype "passive"))
      (node (ref "S213") (pin "2") (pinfunction "2_2") (pintype "passive"))
    )
    (net (code "33") (name "Net-(D214-A)") (class "Default")
      (node (ref "D214") (pin "1") (pinfunction "A_1") (pintype "passive"))
      (node (ref "S214") (pin "1") (pinfunction "1_1") (pintype "passive"))
    )
    (net (code "34") (name "Net-(D215-A)") (class "Default")
      (node (ref "D215") (pin "1") (pinfunction "A_1") (pintype "passive"))
      (node (ref "S215") (pin "2") (pinfunction "2_2") (pintype "passive"))
    )
    (net (code "35") (name "Net-(D216-A)") (class "Default")
      (node (ref "D216") (pin "1") (pinfunction "A_1") (pintype "passive"))
      (node (ref "S216") (pin "1") (pinfunction "1_1") (pintype "passive"))
    )
    (net (code "36") (name "Net-(D217-A)") (class "Default")
      (node (ref "D217") (pin "1") (pinfunction "A_1") (pintype "passive"))
      (node (ref "S217") (pin "2") (pinfunction "2_2") (pintype "passive"))
    )
    (net (code "37") (name "Net-(D218-A)") (class "Default")
      (node (ref "D218") (pin "1") (pinfunction "A_1") (pintype "passive"))
      (node (ref "S218") (pin "1") (pinfunction "1_1") (pintype "passive"))
    )
    (net (code "38") (name "Net-(D219-A)") (class "Default")
      (node (ref "D219") (pin "1") (pinfunction "A_1") (pintype "passive"))
      (node (ref "S219") (pin "2") (pinfunction "2_2") (pintype "passive"))
    )
    (net (code "39") (name "Net-(D220-A)") (class "Default")
      (node (ref "D220") (pin "1") (pinfunction "A_1") (pintype "passive"))
      (node (ref "S220") (pin "1") (pinfunction "1_1") (pintype "passive"))
    )
    (net (code "40") (name "Net-(D221-A)") (class "Default")
      (node (ref "D221") (pin "1") (pinfunction "A_1") (pintype "passive"))
      (node (ref "S221") (pin "2") (pinfunction "2_2") (pintype "passive"))
    )
    (net (code "41") (name "Net-(D222-A)") (class "Default")
      (node (ref "D222") (pin "1") (pinfunction "A_1") (pintype "passive"))
      (node (ref "S222") (pin "1") (pinfunction "1_1") (pintype "passive"))
    )
    (net (code "42") (name "Net-(D223-A)") (class "Default")
      (node (ref "D223") (pin "1") (pinfunction "A_1") (pintype "passive"))
      (node (ref "S223") (pin "2") (pinfunction "2_2") (pintype "passive"))
    )
    (net (code "43") (name "Net-(D224-A)") (class "Default")
      (node (ref "D224") (pin "1") (pinfunction "A_1") (pintype "passive"))
      (node (ref "S224") (pin "1") (pinfunction "1_1") (pintype "passive"))
    )
    (net (code "44") (name "Net-(D225-A)") (class "Default")
      (node (ref "D225") (pin "1") (pinfunction "A_1") (pintype "passive"))
      (node (ref "S225") (pin "2") (pinfunction "2_2") (pintype "passive"))
    )
    (net (code "45") (name "Net-(D226-A)") (class "Default")
      (node (ref "D226") (pin "1") (pinfunction "A_1") (pintype "passive"))
      (node (ref "S226") (pin "1") (pinfunction "1_1") (pintype "passive"))
    )
    (net (code "46") (name "Net-(D227-A)") (class "Default")
      (node (ref "D227") (pin "1") (pinfunction "A_1") (pintype "passive"))
      (node (ref "S227") (pin "1") (pinfunction "1_1") (pintype "passive"))
    )
    (net (code "47") (name "Net-(D228-A)") (class "Default")
      (node (ref "D228") (pin "1") (pinfunction "A_1") (pintype "passive"))
      (node (ref "S228") (pin "1") (pinfunction "1_1") (pintype "passive"))
    )
    (net (code "48") (name "Net-(D229-A)") (class "Default")
      (node (ref "D229") (pin "1") (pinfunction "A_1") (pintype "passive"))
      (node (ref "S229") (pin "2") (pinfunction "2_2") (pintype "passive"))
    )
    (net (code "49") (name "Net-(D230-A)") (class "Default")
      (node (ref "D230") (pin "1") (pinfunction "A_1") (pintype "passive"))
      (node (ref "S230") (pin "1") (pinfunction "1_1") (pintype "passive"))
    )
    (net (code "50") (name "Net-(D231-A)") (class "Default")
      (node (ref "D231") (pin "1") (pinfunction "A_1") (pintype "passive"))
      (node (ref "S231") (pin "2") (pinfunction "2_2") (pintype "passive"))
    )
    (net (code "51") (name "Net-(D232-A)") (class "Default")
      (node (ref "D232") (pin "1") (pinfunction "A_1") (pintype "passive"))
      (node (ref "S232") (pin "1") (pinfunction "1_1") (pintype "passive"))
    )
    (net (code "52") (name "Net-(D233-A)") (class "Default")
      (node (ref "D233") (pin "1") (pinfunction "A_1") (pintype "passive"))
      (node (ref "S233") (pin "2") (pinfunction "2_2") (pintype "passive"))
    )
    (net (code "53") (name "Net-(D234-A)") (class "Default")
      (node (ref "D234") (pin "1") (pinfunction "A_1") (pintype "passive"))
      (node (ref "S234") (pin "2") (pinfunction "2_2") (pintype "passive"))
    )
    (net (code "54") (name "Net-(D235-A)") (class "Default")
      (node (ref "D235") (pin "1") (pinfunction "A_1") (pintype "passive"))
      (node (ref "S235") (pin "1") (pinfunction "1_1") (pintype "passive"))
    )
    (net (code "55") (name "Net-(D236-A)") (class "Default")
      (node (ref "D236") (pin "1") (pinfunction "A_1") (pintype "passive"))
      (node (ref "S236") (pin "2") (pinfunction "2_2") (pintype "passive"))
    )
    (net (code "56") (name "Net-(D237-A)") (class "Default")
      (node (ref "D237") (pin "1") (pinfunction "A_1") (pintype "passive"))
      (node (ref "S237") (pin "1") (pinfunction "1_1") (pintype "passive"))
    )
    (net (code "57") (name "Net-(D238-A)") (class "Default")
      (node (ref "D238") (pin "1") (pinfunction "A_1") (pintype "passive"))
      (node (ref "S238") (pin "1") (pinfunction "1_1") (pintype "passive"))
    )
    (net (code "58") (name "Net-(D239-A)") (class "Default")
      (node (ref "D239") (pin "1") (pinfunction "A_1") (pintype "passive"))
      (node (ref "S239") (pin "2") (pinfunction "2_2") (pintype "passive"))
    )
    (net (code "59") (name "Net-(D240-A)") (class "Default")
      (node (ref "D240") (pin "1") (pinfunction "A_1") (pintype "passive"))
      (node (ref "S240") (pin "1") (pinfunction "1_1") (pintype "passive"))
    )
    (net (code "60") (name "Net-(D241-A)") (class "Default")
      (node (ref "D241") (pin "1") (pinfunction "A_1") (pintype "passive"))
      (node (ref "S241") (pin "2") (pinfunction "2_2") (pintype "passive"))
    )
    (net (code "61") (name "Net-(D242-A)") (class "Default")
      (node (ref "D242") (pin "1") (pinfunction "A_1") (pintype "passive"))
      (node (ref "S242") (pin "2") (pinfunction "2_2") (pintype "passive"))
    )
    (net (code "62") (name "Net-(D243-A)") (class "Default")
      (node (ref "D243") (pin "1") (pinfunction "A_1") (pintype "passive"))
      (node (ref "S243") (pin "1") (pinfunction "1_1") (pintype "passive"))
    )
    (net (code "63") (name "Net-(D244-A)") (class "Default")
      (node (ref "D244") (pin "1") (pinfunction "A_1") (pintype "passive"))
      (node (ref "S244") (pin "1") (pinfunction "1_1") (pintype "passive"))
    )
    (net (code "64") (name "Net-(D245-A)") (class "Default")
      (node (ref "D245") (pin "1") (pinfunction "A_1") (pintype "passive"))
      (node (ref "S245") (pin "2") (pinfunction "2_2") (pintype "passive"))
    )
    (net (code "65") (name "Net-(D246-A)") (class "Default")
      (node (ref "D246") (pin "1") (pinfunction "A_1") (pintype "passive"))
      (node (ref "S246") (pin "1") (pinfunction "1_1") (pintype "passive"))
    )
    (net (code "66") (name "Net-(D247-A)") (class "Default")
      (node (ref "D247") (pin "1") (pinfunction "A_1") (pintype "passive"))
      (node (ref "S247") (pin "2") (pinfunction "2_2") (pintype "passive"))
    )
    (net (code "67") (name "Net-(D248-A)") (class "Default")
      (node (ref "D248") (pin "1") (pinfunction "A_1") (pintype "passive"))
      (node (ref "S248") (pin "1") (pinfunction "1_1") (pintype "passive"))
    )
    (net (code "68") (name "Net-(D249-A)") (class "Default")
      (node (ref "D249") (pin "1") (pinfunction "A_1") (pintype "passive"))
      (node (ref "S249") (pin "1") (pinfunction "1_1") (pintype "passive"))
    )
    (net (code "69") (name "Net-(D250-A)") (class "Default")
      (node (ref "D250") (pin "1") (pinfunction "A_1") (pintype "passive"))
      (node (ref "S250") (pin "1") (pinfunction "1_1") (pintype "passive"))
    )
    (net (code "70") (name "Net-(D251-A)") (class "Default")
      (node (ref "D251") (pin "1") (pinfunction "A_1") (pintype "passive"))
      (node (ref "S251") (pin "1") (pinfunction "1_1") (pintype "passive"))
    )
    (net (code "71") (name "Net-(D252-A)") (class "Default")
      (node (ref "D252") (pin "1") (pinfunction "A_1") (pintype "passive"))
      (node (ref "S252") (pin "1") (pinfunction "1_1") (pintype "passive"))
    )
    (net (code "72") (name "Net-(D253-A)") (class "Default")
      (node (ref "D253") (pin "1") (pinfunction "A_1") (pintype "passive"))
      (node (ref "S253") (pin "2") (pinfunction "2_2") (pintype "passive"))
    )
    (net (code "73") (name "Net-(D254-A)") (class "Default")
      (node (ref "D254") (pin "1") (pinfunction "A_1") (pintype "passive"))
      (node (ref "S254") (pin "1") (pinfunction "1_1") (pintype "passive"))
    )
    (net (code "74") (name "Net-(D255-A)") (class "Default")
      (node (ref "D255") (pin "1") (pinfunction "A_1") (pintype "passive"))
      (node (ref "S255") (pin "1") (pinfunction "1_1") (pintype "passive"))
    )
    (net (code "75") (name "Net-(D256-A)") (class "Default")
      (node (ref "D256") (pin "1") (pinfunction "A_1") (pintype "passive"))
      (node (ref "S256") (pin "2") (pinfunction "2_2") (pintype "passive"))
    )
    (net (code "76") (name "Net-(D257-A)") (class "Default")
      (node (ref "D257") (pin "1") (pinfunction "A_1") (pintype "passive"))
      (node (ref "S257") (pin "2") (pinfunction "2_2") (pintype "passive"))
    )
    (net (code "77") (name "Net-(D258-A)") (class "Default")
      (node (ref "D258") (pin "1") (pinfunction "A_1") (pintype "passive"))
      (node (ref "S258") (pin "1") (pinfunction "1_1") (pintype "passive"))
    )
    (net (code "78") (name "Net-(D259-A)") (class "Default")
      (node (ref "D259") (pin "1") (pinfunction "A_1") (pintype "passive"))
      (node (ref "S259") (pin "2") (pinfunction "2_2") (pintype "passive"))
    )
    (net (code "79") (name "Net-(D260-A)") (class "Default")
      (node (ref "D260") (pin "1") (pinfunction "A_1") (pintype "passive"))
      (node (ref "S260") (pin "2") (pinfunction "2_2") (pintype "passive"))
    )
    (net (code "80") (name "Net-(D261-A)") (class "Default")
      (node (ref "D261") (pin "1") (pinfunction "A_1") (pintype "passive"))
      (node (ref "S261") (pin "1") (pinfunction "1_1") (pintype "passive"))
    )
    (net (code "81") (name "Net-(D262-A)") (class "Default")
      (node (ref "D262") (pin "1") (pinfunction "A_1") (pintype "passive"))
      (node (ref "S262") (pin "1") (pinfunction "1_1") (pintype "passive"))
    )
    (net (code "82") (name "Net-(D263-A)") (class "Default")
      (node (ref "D263") (pin "1") (pinfunction "A_1") (pintype "passive"))
      (node (ref "S263") (pin "1") (pinfunction "1_1") (pintype "passive"))
    )
    (net (code "83") (name "Net-(D264-A)") (class "Default")
      (node (ref "D264") (pin "1") (pinfunction "A_1") (pintype "passive"))
      (node (ref "S264") (pin "1") (pinfunction "1_1") (pintype "passive"))
    )
  )
)
